# enginecontrol.net
KiCad netlist of a schematic drawn in EAGLE
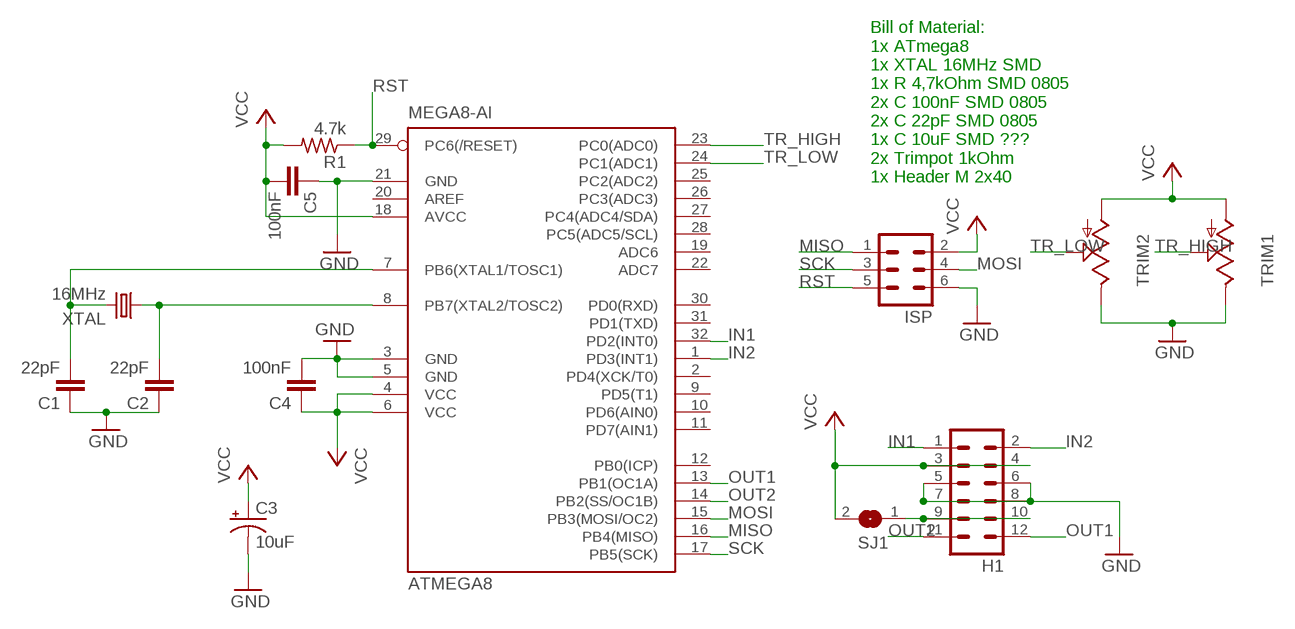
[diagram p0: schematic, sheet 1]

(export (version "E")
  (design (tool "Eeschema 10.0.6"))
  (components
    (comp (ref "ATMEGA8")
      (value "MEGA8-AI")
      (footprint "eagle-import:TQFP32-08")
      (fields (field (name "MPN") "ATMEGA8-16AU"))
      (libsource (lib "eagle-import") (part "MEGA8-AI"))
    )
    (comp (ref "C1")
      (value "22pF")
      (footprint "eagle-import:C0805")
      (libsource (lib "eagle-import") (part "C-EUC0805"))
    )
    (comp (ref "C2")
      (value "22pF")
      (footprint "eagle-import:C0805")
      (libsource (lib "eagle-import") (part "C-EUC0805"))
    )
    (comp (ref "C3")
      (value "10uF")
      (footprint "eagle-import:153CLV-0605")
      (libsource (lib "eagle-import") (part "CPOL-US153CLV-0605"))
    )
    (comp (ref "C4")
      (value "100nF")
      (footprint "eagle-import:C0805")
      (libsource (lib "eagle-import") (part "C-EUC0805"))
    )
    (comp (ref "C5")
      (value "100nF")
      (footprint "eagle-import:C0805")
      (libsource (lib "eagle-import") (part "C-EUC0805"))
    )
    (comp (ref "H1")
      (value "MA06-2")
      (footprint "eagle-import:MA06-2")
      (libsource (lib "eagle-import") (part "MA06-2"))
    )
    (comp (ref "ISP")
      (value "MA03-2")
      (footprint "eagle-import:MA03-2")
      (libsource (lib "eagle-import") (part "MA03-2"))
    )
    (comp (ref "R1")
      (value "4.7k")
      (footprint "eagle-import:M0805")
      (libsource (lib "eagle-import") (part "R-US_M0805"))
    )
    (comp (ref "SJ1") (value "SJ") (footprint "eagle-import:SJ") (libsource (lib "eagle-import") (part "SJ")))
    (comp (ref "TRIM1")
      (value "TRIM_US-B25P")
      (footprint "eagle-import:B25P")
      (libsource (lib "eagle-import") (part "TRIM_US-B25P"))
    )
    (comp (ref "TRIM2")
      (value "TRIM_US-B25P")
      (footprint "eagle-import:B25P")
      (libsource (lib "eagle-import") (part "TRIM_US-B25P"))
    )
    (comp (ref "XTAL")
      (value "16MHz")
      (footprint "eagle-import:SM49")
      (libsource (lib "eagle-import") (part "CRYSTALSM49"))
    )
  )
  (nets
    (net (code "1") (name "/IN1") (class "Default")
      (node (ref "ATMEGA8") (pin "32") (pinfunction "PD2(INT0)_32") (pintype "bidirectional"))
      (node (ref "H1") (pin "1") (pinfunction "1_1") (pintype "passive"))
    )
    (net (code "2") (name "/IN2") (class "Default")
      (node (ref "ATMEGA8") (pin "1") (pinfunction "PD3(INT1)_1") (pintype "bidirectional"))
      (node (ref "H1") (pin "2") (pinfunction "2_2") (pintype "passive"))
    )
    (net (code "3") (name "/MISO") (class "Default")
      (node (ref "ATMEGA8") (pin "16") (pinfunction "PB4(MISO)_16") (pintype "bidirectional"))
      (node (ref "ISP") (pin "1") (pinfunction "1_1") (pintype "passive"))
    )
    (net (code "4") (name "/MOSI") (class "Default")
      (node (ref "ATMEGA8") (pin "15") (pinfunction "PB3(MOSI/OC2)_15") (pintype "bidirectional"))
      (node (ref "ISP") (pin "4") (pinfunction "4_4") (pintype "passive"))
    )
    (net (code "5") (name "/OUT1") (class "Default")
      (node (ref "ATMEGA8") (pin "13") (pinfunction "PB1(OC1A)_13") (pintype "bidirectional"))
      (node (ref "H1") (pin "12") (pinfunction "12_12") (pintype "passive"))
    )
    (net (code "6") (name "/OUT2") (class "Default")
      (node (ref "ATMEGA8") (pin "14") (pinfunction "PB2(SS/OC1B)_14") (pintype "bidirectional"))
      (node (ref "H1") (pin "11") (pinfunction "11_11") (pintype "passive"))
    )
    (net (code "7") (name "/RST") (class "Default")
      (node (ref "ATMEGA8") (pin "29") (pinfunction "PC6(/RESET)_29") (pintype "bidirectional"))
      (node (ref "ISP") (pin "5") (pinfunction "5_5") (pintype "passive"))
      (node (ref "R1") (pin "1") (pinfunction "1_1") (pintype "passive"))
    )
    (net (code "8") (name "/SCK") (class "Default")
      (node (ref "ATMEGA8") (pin "17") (pinfunction "PB5(SCK)_17") (pintype "bidirectional"))
      (node (ref "ISP") (pin "3") (pinfunction "3_3") (pintype "passive"))
    )
    (net (code "9") (name "/TR_HIGH") (class "Default")
      (node (ref "ATMEGA8") (pin "23") (pinfunction "PC0(ADC0)_23") (pintype "bidirectional"))
      (node (ref "TRIM1") (pin "S") (pinfunction "S_S") (pintype "passive"))
    )
    (net (code "10") (name "/TR_LOW") (class "Default")
      (node (ref "ATMEGA8") (pin "24") (pinfunction "PC1(ADC1)_24") (pintype "bidirectional"))
      (node (ref "TRIM2") (pin "S") (pinfunction "S_S") (pintype "passive"))
    )
    (net (code "11") (name "GND") (class "Default")
      (node (ref "ATMEGA8") (pin "21") (pinfunction "GND_21") (pintype "power_in"))
      (node (ref "ATMEGA8") (pin "3") (pinfunction "GND_3") (pintype "power_in"))
      (node (ref "ATMEGA8") (pin "5") (pinfunction "GND_5") (pintype "power_in"))
      (node (ref "C1") (pin "1") (pinfunction "1_1") (pintype "passive"))
      (node (ref "C2") (pin "1") (pinfunction "1_1") (pintype "passive"))
      (node (ref "C3") (pin "-") (pinfunction "-_-") (pintype "passive"))
      (node (ref "C4") (pin "2") (pinfunction "2_2") (pintype "passive"))
      (node (ref "C5") (pin "1") (pinfunction "1_1") (pintype "passive"))
      (node (ref "H1") (pin "5") (pinfunction "5_5") (pintype "passive"))
      (node (ref "H1") (pin "6") (pinfunction "6_6") (pintype "passive"))
      (node (ref "H1") (pin "7") (pinfunction "7_7") (pintype "passive"))
      (node (ref "H1") (pin "8") (pinfunction "8_8") (pintype "passive"))
      (node (ref "ISP") (pin "6") (pinfunction "6_6") (pintype "passive"))
      (node (ref "TRIM1") (pin "E") (pinfunction "E_E") (pintype "passive"))
      (node (ref "TRIM2") (pin "E") (pinfunction "E_E") (pintype "passive"))
    )
    (net (code "12") (name "Net-(ATMEGA8-PB6(XTAL1{slash}TOSC1))") (class "Default")
      (node (ref "ATMEGA8") (pin "7") (pinfunction "PB6(XTAL1/TOSC1)_7") (pintype "bidirectional"))
      (node (ref "C1") (pin "2") (pinfunction "2_2") (pintype "passive"))
      (node (ref "XTAL") (pin "2") (pinfunction "2_2") (pintype "passive"))
    )
    (net (code "13") (name "Net-(ATMEGA8-PB7(XTAL2{slash}TOSC2))") (class "Default")
      (node (ref "ATMEGA8") (pin "8") (pinfunction "PB7(XTAL2/TOSC2)_8") (pintype "bidirectional"))
      (node (ref "C2") (pin "2") (pinfunction "2_2") (pintype "passive"))
      (node (ref "XTAL") (pin "1") (pinfunction "1_1") (pintype "passive"))
    )
    (net (code "14") (name "Net-(H1-Pad10)") (class "Default")
      (node (ref "H1") (pin "10") (pinfunction "10_10") (pintype "passive"))
      (node (ref "H1") (pin "9") (pinfunction "9_9") (pintype "passive"))
      (node (ref "SJ1") (pin "1") (pinfunction "1_1") (pintype "passive"))
    )
    (net (code "15") (name "VCC") (class "Default")
      (node (ref "ATMEGA8") (pin "18") (pinfunction "AVCC_18") (pintype "power_in"))
      (node (ref "ATMEGA8") (pin "4") (pinfunction "VCC_4") (pintype "power_in"))
      (node (ref "ATMEGA8") (pin "6") (pinfunction "VCC_6") (pintype "power_in"))
      (node (ref "C3") (pin "+") (pinfunction "+_+") (pintype "passive"))
      (node (ref "C4") (pin "1") (pinfunction "1_1") (pintype "passive"))
      (node (ref "C5") (pin "2") (pinfunction "2_2") (pintype "passive"))
      (node (ref "H1") (pin "3") (pinfunction "3_3") (pintype "passive"))
      (node (ref "H1") (pin "4") (pinfunction "4_4") (pintype "passive"))
      (node (ref "ISP") (pin "2") (pinfunction "2_2") (pintype "passive"))
      (node (ref "R1") (pin "2") (pinfunction "2_2") (pintype "passive"))
      (node (ref "SJ1") (pin "2") (pinfunction "2_2") (pintype "passive"))
      (node (ref "TRIM1") (pin "A") (pinfunction "A_A") (pintype "passive"))
      (node (ref "TRIM2") (pin "A") (pinfunction "A_A") (pintype "passive"))
    )
    (net (code "16") (name "unconnected-(ATMEGA8-ADC6-Pad19)") (class "Default")
      (node (ref "ATMEGA8") (pin "19") (pinfunction "ADC6_19") (pintype "bidirectional"))
    )
    (net (code "17") (name "unconnected-(ATMEGA8-ADC7-Pad22)") (class "Default")
      (node (ref "ATMEGA8") (pin "22") (pinfunction "ADC7_22") (pintype "bidirectional"))
    )
    (net (code "18") (name "unconnected-(ATMEGA8-AREF-Pad20)") (class "Default")
      (node (ref "ATMEGA8") (pin "20") (pinfunction "AREF_20") (pintype "passive"))
    )
    (net (code "19") (name "unconnected-(ATMEGA8-PB0(ICP)-Pad12)") (class "Default")
      (node (ref "ATMEGA8") (pin "12") (pinfunction "PB0(ICP)_12") (pintype "bidirectional"))
    )
    (net (code "20") (name "unconnected-(ATMEGA8-PC2(ADC2)-Pad25)") (class "Default")
      (node (ref "ATMEGA8") (pin "25") (pinfunction "PC2(ADC2)_25") (pintype "bidirectional"))
    )
    (net (code "21") (name "unconnected-(ATMEGA8-PC3(ADC3)-Pad26)") (class "Default")
      (node (ref "ATMEGA8") (pin "26") (pinfunction "PC3(ADC3)_26") (pintype "bidirectional"))
    )
    (net (code "22") (name "unconnected-(ATMEGA8-PC4(ADC4{slash}SDA)-Pad27)") (class "Default")
      (node (ref "ATMEGA8") (pin "27") (pinfunction "PC4(ADC4/SDA)_27") (pintype "bidirectional"))
    )
    (net (code "23") (name "unconnected-(ATMEGA8-PC5(ADC5{slash}SCL)-Pad28)") (class "Default")
      (node (ref "ATMEGA8") (pin "28") (pinfunction "PC5(ADC5/SCL)_28") (pintype "bidirectional"))
    )
    (net (code "24") (name "unconnected-(ATMEGA8-PD0(RXD)-Pad30)") (class "Default")
      (node (ref "ATMEGA8") (pin "30") (pinfunction "PD0(RXD)_30") (pintype "bidirectional"))
    )
    (net (code "25") (name "unconnected-(ATMEGA8-PD1(TXD)-Pad31)") (class "Default")
      (node (ref "ATMEGA8") (pin "31") (pinfunction "PD1(TXD)_31") (pintype "bidirectional"))
    )
    (net (code "26") (name "unconnected-(ATMEGA8-PD4(XCK{slash}T0)-Pad2)") (class "Default")
      (node (ref "ATMEGA8") (pin "2") (pinfunction "PD4(XCK/T0)_2") (pintype "bidirectional"))
    )
    (net (code "27") (name "unconnected-(ATMEGA8-PD5(T1)-Pad9)") (class "Default")
      (node (ref "ATMEGA8") (pin "9") (pinfunction "PD5(T1)_9") (pintype "bidirectional"))
    )
    (net (code "28") (name "unconnected-(ATMEGA8-PD6(AIN0)-Pad10)") (class "Default")
      (node (ref "ATMEGA8") (pin "10") (pinfunction "PD6(AIN0)_10") (pintype "bidirectional"))
    )
    (net (code "29") (name "unconnected-(ATMEGA8-PD7(AIN1)-Pad11)") (class "Default")
      (node (ref "ATMEGA8") (pin "11") (pinfunction "PD7(AIN1)_11") (pintype "bidirectional"))
    )
  )
)
